# 5vacnew.net
KiCad netlist of a schematic drawn in EAGLE
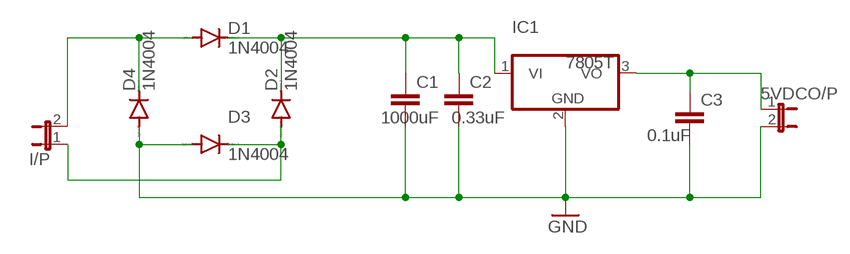
[diagram p0: schematic, sheet 1]

(export (version "E")
  (design (tool "Eeschema 10.0.6"))
  (components
    (comp (ref "5VDCO/P")
      (value "JP1E")
      (footprint "eagle-import:JP1")
      (libsource (lib "eagle-import") (part "JP1E"))
    )
    (comp (ref "C1")
      (value "1000uF")
      (footprint "eagle-import:C2.5-3")
      (libsource (lib "eagle-import") (part "C2,5-3"))
    )
    (comp (ref "C2")
      (value "0.33uF")
      (footprint "eagle-import:C2.5-3")
      (libsource (lib "eagle-import") (part "C2,5-3"))
    )
    (comp (ref "C3")
      (value "0.1uF")
      (footprint "eagle-import:C2.5-3")
      (libsource (lib "eagle-import") (part "C2,5-3"))
    )
    (comp (ref "D1")
      (value "1N4004")
      (footprint "eagle-import:DO41-10")
      (libsource (lib "eagle-import") (part "1N4004"))
    )
    (comp (ref "D2")
      (value "1N4004")
      (footprint "eagle-import:DO41-10")
      (libsource (lib "eagle-import") (part "1N4004"))
    )
    (comp (ref "D3")
      (value "1N4004")
      (footprint "eagle-import:DO41-10")
      (libsource (lib "eagle-import") (part "1N4004"))
    )
    (comp (ref "D4")
      (value "1N4004")
      (footprint "eagle-import:DO41-10")
      (libsource (lib "eagle-import") (part "1N4004"))
    )
    (comp (ref "I/P")
      (value "JP1E")
      (footprint "eagle-import:JP1")
      (libsource (lib "eagle-import") (part "JP1E"))
    )
    (comp (ref "IC1")
      (value "7805T")
      (footprint "eagle-import:TO220H")
      (libsource (lib "eagle-import") (part "78T05"))
    )
  )
  (nets
    (net (code "1") (name "GND") (class "Default")
      (node (ref "5VDCO/P") (pin "2") (pinfunction "2_2") (pintype "passive"))
      (node (ref "C1") (pin "2") (pinfunction "2_2") (pintype "passive"))
      (node (ref "C2") (pin "2") (pinfunction "2_2") (pintype "passive"))
      (node (ref "C3") (pin "2") (pinfunction "2_2") (pintype "passive"))
      (node (ref "D3") (pin "A") (pinfunction "A_A") (pintype "passive"))
      (node (ref "D4") (pin "A") (pinfunction "A_A") (pintype "passive"))
      (node (ref "IC1") (pin "2") (pinfunction "GND_2") (pintype "passive"))
    )
    (net (code "2") (name "Net-(D1-PadA)") (class "Default")
      (node (ref "D1") (pin "A") (pinfunction "A_A") (pintype "passive"))
      (node (ref "D4") (pin "C") (pinfunction "C_C") (pintype "passive"))
      (node (ref "I/P") (pin "2") (pinfunction "2_2") (pintype "passive"))
    )
    (net (code "3") (name "Net-(D2-PadA)") (class "Default")
      (node (ref "D2") (pin "A") (pinfunction "A_A") (pintype "passive"))
      (node (ref "D3") (pin "C") (pinfunction "C_C") (pintype "passive"))
      (node (ref "I/P") (pin "1") (pinfunction "1_1") (pintype "passive"))
    )
    (net (code "4") (name "Net-(IC1-VI)") (class "Default")
      (node (ref "C1") (pin "1") (pinfunction "1_1") (pintype "passive"))
      (node (ref "C2") (pin "1") (pinfunction "1_1") (pintype "passive"))
      (node (ref "D1") (pin "C") (pinfunction "C_C") (pintype "passive"))
      (node (ref "D2") (pin "C") (pinfunction "C_C") (pintype "passive"))
      (node (ref "IC1") (pin "1") (pinfunction "VI_1") (pintype "input"))
    )
    (net (code "5") (name "Net-(IC1-VO)") (class "Default")
      (node (ref "5VDCO/P") (pin "1") (pinfunction "1_1") (pintype "passive"))
      (node (ref "C3") (pin "1") (pinfunction "1_1") (pintype "passive"))
      (node (ref "IC1") (pin "3") (pinfunction "VO_3") (pintype "passive"))
    )
  )
)
